# FPGA.net
KiCad netlist of a schematic drawn in Altium Designer
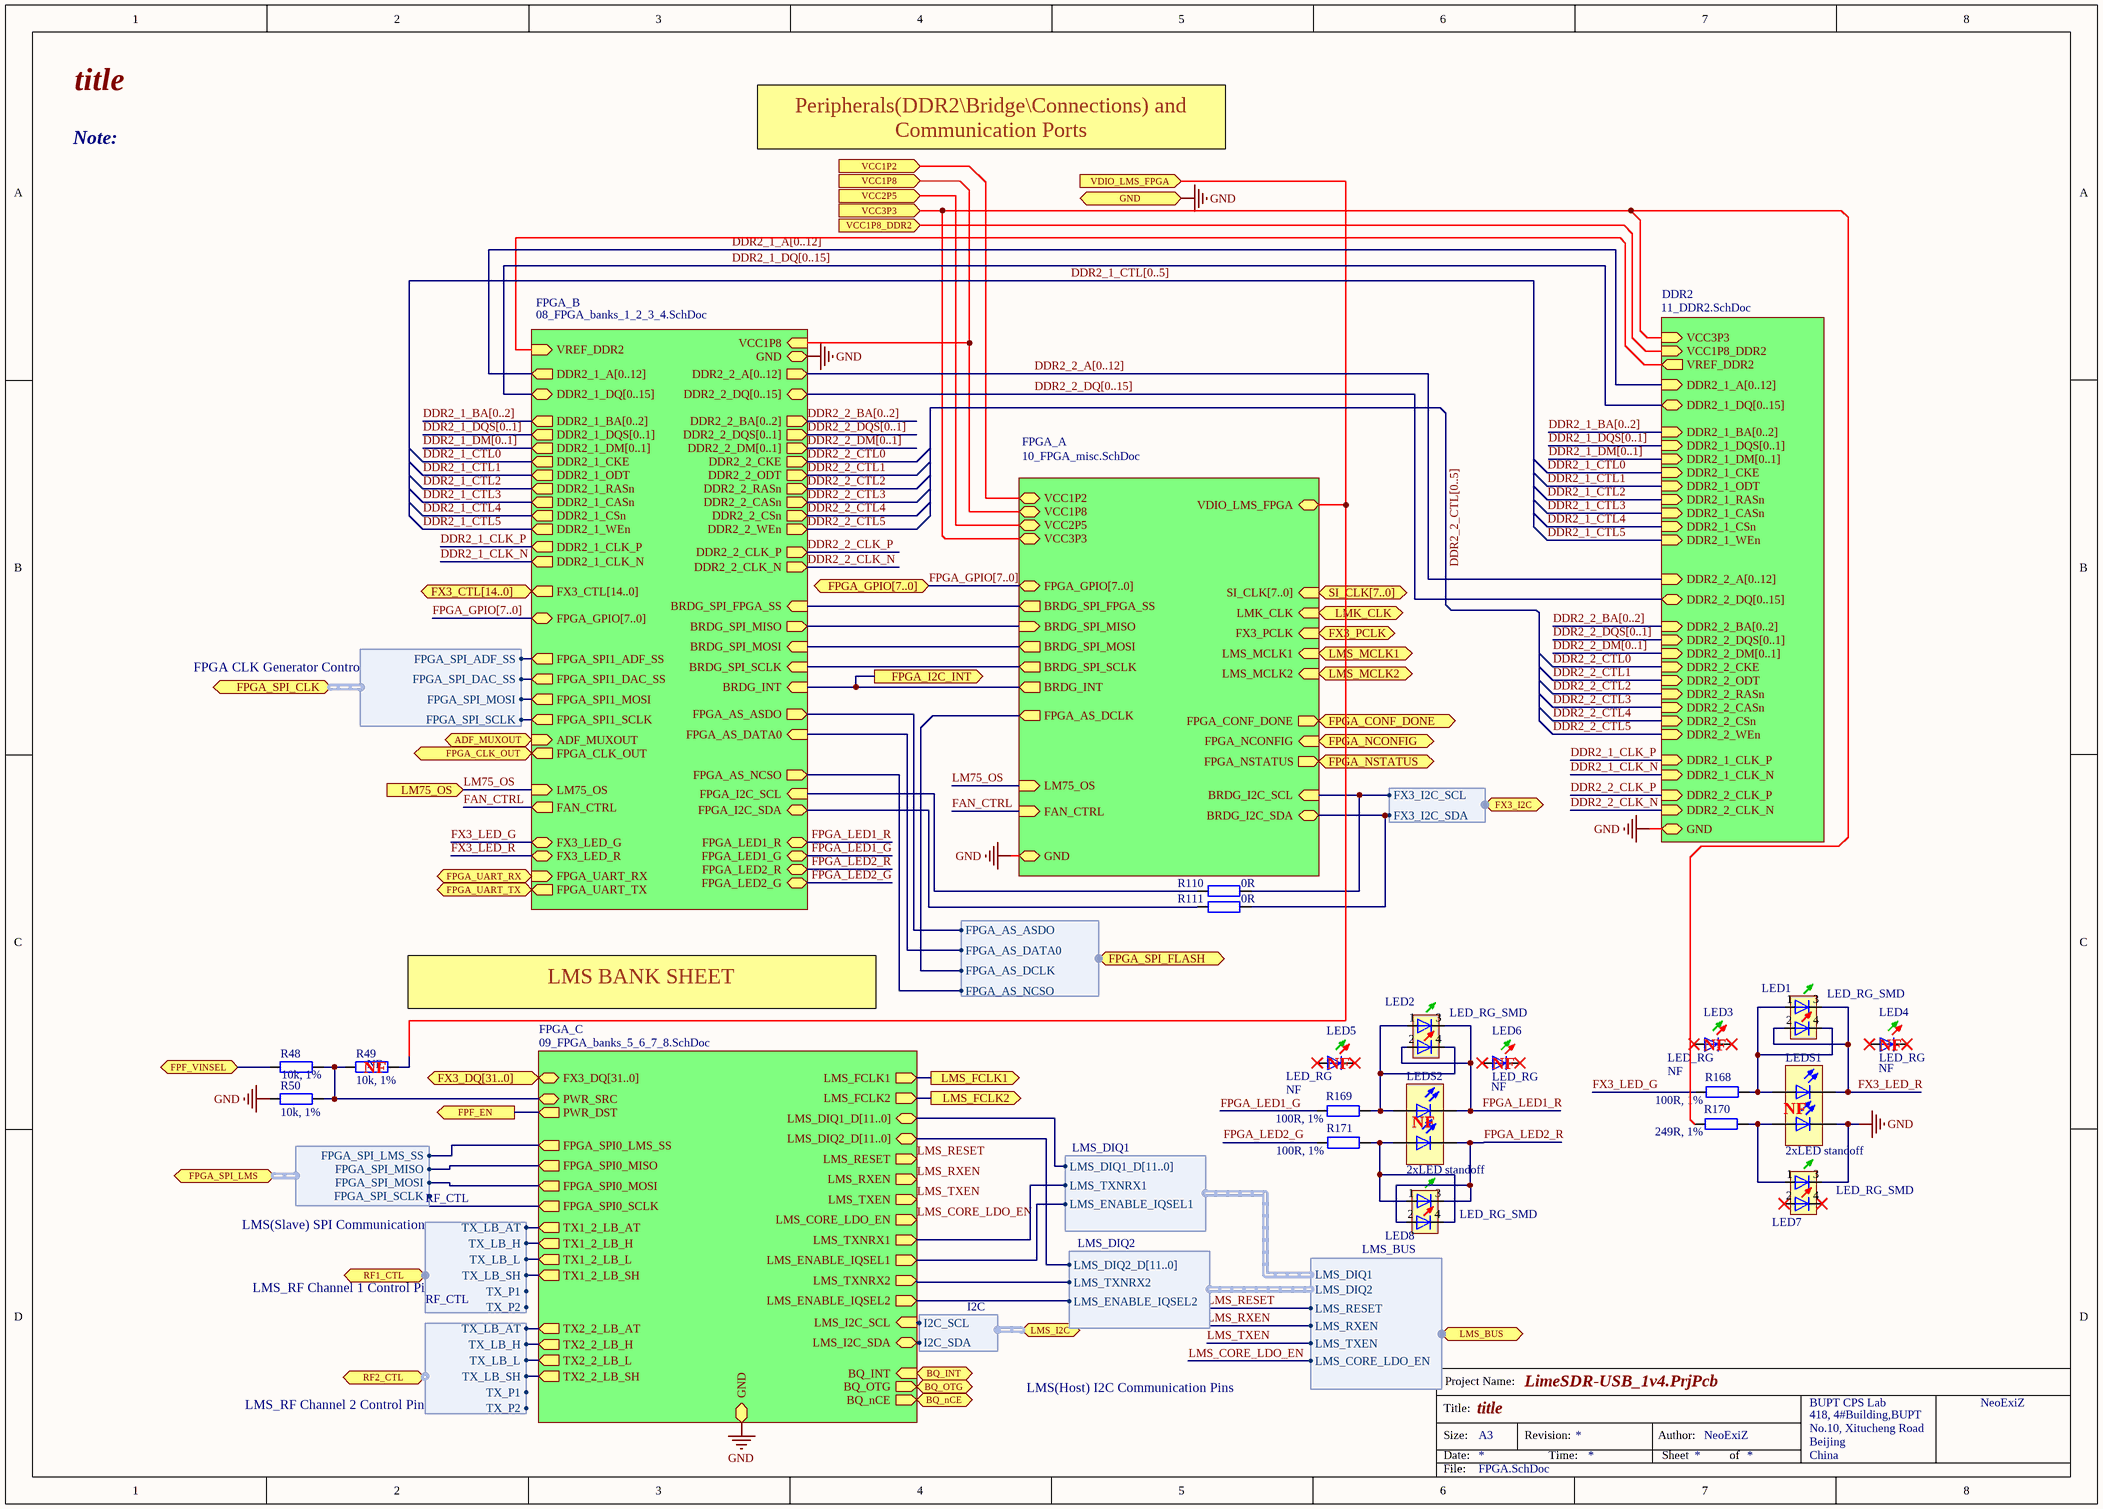
[diagram p0: FPGA.SchDoc]

(export (version "E")
  (design (tool "Eeschema 10.0.6"))
  (components
    (comp (ref "LED1")
      (value "LED_RG_SMD")
      (footprint "LED-2x0603")
      (fields (field (name "MANUFACTURER") "Avago Technologies US Inc."))
      (libsource (lib "LimeMicroAltiumLib_schLib") (part "LED_green_red_SMD"))
    )
    (comp (ref "LED2")
      (value "LED_RG_SMD")
      (footprint "LED-2x0603")
      (fields (field (name "MANUFACTURER") "Avago Technologies US Inc."))
      (libsource (lib "LimeMicroAltiumLib_schLib") (part "LED_green_red_SMD"))
    )
    (comp (ref "LED3")
      (value "LED_RG")
      (fields
        (field (name "MANUFACTURER") "Visual Communications Company - VCC")
        (field (name "ASSEMBLY INFO") "NF")
      )
      (libsource (lib "LimeMicroAltiumLib_schLib") (part "LED_green_red"))
    )
    (comp (ref "LED4")
      (value "LED_RG")
      (fields
        (field (name "MANUFACTURER") "Visual Communications Company - VCC")
        (field (name "ASSEMBLY INFO") "NF")
      )
      (libsource (lib "LimeMicroAltiumLib_schLib") (part "LED_green_red"))
    )
    (comp (ref "LED5")
      (value "LED_RG")
      (fields
        (field (name "MANUFACTURER") "Visual Communications Company - VCC")
        (field (name "ASSEMBLY INFO") "NF")
      )
      (libsource (lib "LimeMicroAltiumLib_schLib") (part "LED_green_red"))
    )
    (comp (ref "LED6")
      (value "LED_RG")
      (fields
        (field (name "MANUFACTURER") "Visual Communications Company - VCC")
        (field (name "ASSEMBLY INFO") "NF")
      )
      (libsource (lib "LimeMicroAltiumLib_schLib") (part "LED_green_red"))
    )
    (comp (ref "LED7")
      (value "LED_RG_SMD")
      (footprint "LED-2x0603")
      (fields (field (name "MANUFACTURER") "Avago Technologies US Inc."))
      (libsource (lib "LimeMicroAltiumLib_schLib") (part "LED_green_red_SMD"))
    )
    (comp (ref "LED8")
      (value "LED_RG_SMD")
      (footprint "LED-2x0603")
      (fields (field (name "MANUFACTURER") "Avago Technologies US Inc."))
      (libsource (lib "LimeMicroAltiumLib_schLib") (part "LED_green_red_SMD"))
    )
    (comp (ref "LEDS1")
      (value "2xLED standoff")
      (footprint "LED_STANDOFF_H-201C")
      (libsource (lib "LimeMicroAltiumLib_schLib") (part "LEDx2_STANDOFF"))
    )
    (comp (ref "LEDS2")
      (value "2xLED standoff")
      (footprint "LED_STANDOFF_H-201C")
      (libsource (lib "LimeMicroAltiumLib_schLib") (part "LEDx2_STANDOFF"))
    )
    (comp (ref "R48")
      (value "10k, 1%")
      (footprint "RES0402")
      (fields (field (name "MANUFACTURER") "Yageo") (field (name "TOLERANCE") "±1%"))
      (libsource (lib "LimeMicroAltiumLib_schLib") (part "Res_0402"))
    )
    (comp (ref "R49")
      (value "10k, 1%")
      (footprint "RES0402")
      (fields
        (field (name "ASSEMBLY INFO") "NF")
        (field (name "MANUFACTURER") "Yageo")
        (field (name "TOLERANCE") "±1%")
      )
      (libsource (lib "LimeMicroAltiumLib_schLib") (part "Res_0402"))
    )
    (comp (ref "R50")
      (value "10k, 1%")
      (footprint "RES0402")
      (fields (field (name "MANUFACTURER") "Yageo") (field (name "TOLERANCE") "±1%"))
      (libsource (lib "LimeMicroAltiumLib_schLib") (part "Res_0402"))
    )
    (comp (ref "R110")
      (value "0R")
      (footprint "RES0402")
      (fields (field (name "MANUFACTURER") "Yageo"))
      (libsource (lib "LimeFPGAboard_schLib") (part "Res_0402"))
    )
    (comp (ref "R111")
      (value "0R")
      (footprint "RES0402")
      (fields (field (name "MANUFACTURER") "Yageo"))
      (libsource (lib "LimeFPGAboard_schLib") (part "Res_0402"))
    )
    (comp (ref "R168")
      (value "100R, 1%")
      (footprint "RES0402")
      (fields (field (name "TOLERANCE") "±1%") (field (name "MANUFACTURER") "Stackpole Electronics Inc."))
      (libsource (lib "LimeMicroAltiumLib_schLib") (part "Res_0402"))
    )
    (comp (ref "R169")
      (value "100R, 1%")
      (footprint "RES0402")
      (fields (field (name "TOLERANCE") "±1%") (field (name "MANUFACTURER") "Stackpole Electronics Inc."))
      (libsource (lib "LimeMicroAltiumLib_schLib") (part "Res_0402"))
    )
    (comp (ref "R170")
      (value "249R, 1%")
      (footprint "RES0402")
      (fields (field (name "MANUFACTURER") "Stackpole Electronics Inc") (field (name "TOLERANCE") "±1%"))
      (libsource (lib "LimeMicroAltiumLib_schLib") (part "Res_0402"))
    )
    (comp (ref "R171")
      (value "100R, 1%")
      (footprint "RES0402")
      (fields (field (name "TOLERANCE") "±1%") (field (name "MANUFACTURER") "Stackpole Electronics Inc."))
      (libsource (lib "LimeMicroAltiumLib_schLib") (part "Res_0402"))
    )
  )
  (nets
    (net (code "149") (name "/BRDG_I2C_SCL") (class "Default")
      (node (ref "R110") (pin "2") (pinfunction "2_2") (pintype "passive"))
    )
    (net (code "150") (name "/BRDG_I2C_SDA") (class "Default")
      (node (ref "R111") (pin "2") (pinfunction "2_2") (pintype "passive"))
    )
    (net (code "185") (name "/FPF_VINSEL") (class "Default")
      (node (ref "R48") (pin "1") (pinfunction "1_1") (pintype "passive"))
    )
    (net (code "194") (name "/FPGA_I2C_SCL") (class "Default")
      (node (ref "R110") (pin "1") (pinfunction "1_1") (pintype "passive"))
    )
    (net (code "195") (name "/FPGA_I2C_SDA") (class "Default")
      (node (ref "R111") (pin "1") (pinfunction "1_1") (pintype "passive"))
    )
    (net (code "196") (name "/FPGA_LED1_G") (class "Default")
      (node (ref "R169") (pin "1") (pinfunction "1_1") (pintype "passive"))
    )
    (net (code "197") (name "/FPGA_LED1_R") (class "Default")
      (node (ref "LED2") (pin "2") (pinfunction "2_2") (pintype "power_in"))
      (node (ref "LED2") (pin "3") (pinfunction "3_3") (pintype "power_in"))
      (node (ref "LEDS2") (pin "K1") (pinfunction "C_K1") (pintype "power_in"))
    )
    (net (code "198") (name "/FPGA_LED2_G") (class "Default")
      (node (ref "R171") (pin "1") (pinfunction "1_1") (pintype "passive"))
    )
    (net (code "199") (name "/FPGA_LED2_R") (class "Default")
      (node (ref "LED8") (pin "2") (pinfunction "2_2") (pintype "power_in"))
      (node (ref "LED8") (pin "3") (pinfunction "3_3") (pintype "power_in"))
      (node (ref "LEDS2") (pin "K2") (pinfunction "C_K2") (pintype "power_in"))
    )
    (net (code "214") (name "/FX3_LED_G") (class "Default")
      (node (ref "R168") (pin "1") (pinfunction "1_1") (pintype "passive"))
    )
    (net (code "215") (name "/FX3_LED_R") (class "Default")
      (node (ref "LED1") (pin "2") (pinfunction "2_2") (pintype "power_in"))
      (node (ref "LED1") (pin "3") (pinfunction "3_3") (pintype "power_in"))
      (node (ref "LEDS1") (pin "K1") (pinfunction "C_K1") (pintype "power_in"))
    )
    (net (code "236") (name "/PWR_SRC") (class "Default")
      (node (ref "R48") (pin "2") (pinfunction "2_2") (pintype "passive"))
      (node (ref "R49") (pin "1") (pinfunction "1_1") (pintype "passive"))
      (node (ref "R50") (pin "2") (pinfunction "2_2") (pintype "passive"))
    )
    (net (code "250") (name "/VCC3P3") (class "Default")
      (node (ref "R170") (pin "1") (pinfunction "1_1") (pintype "passive"))
    )
    (net (code "251") (name "/VDIO_LMS_FPGA") (class "Default")
      (node (ref "R49") (pin "2") (pinfunction "2_2") (pintype "passive"))
    )
    (net (code "261") (name "GND") (class "Default")
      (node (ref "LED7") (pin "3") (pinfunction "3_3") (pintype "power_in"))
      (node (ref "LEDS1") (pin "K2") (pinfunction "C_K2") (pintype "power_in"))
      (node (ref "R50") (pin "1") (pinfunction "1_1") (pintype "passive"))
    )
    (net (code "262") (name "Net-(LED1-Pad1)") (class "Default")
      (node (ref "LED1") (pin "1") (pinfunction "1_1") (pintype "power_in"))
      (node (ref "LED1") (pin "4") (pinfunction "4_4") (pintype "power_in"))
      (node (ref "LEDS1") (pin "A1") (pinfunction "A_A1") (pintype "power_in"))
      (node (ref "R168") (pin "2") (pinfunction "2_2") (pintype "passive"))
    )
    (net (code "263") (name "Net-(LED2-Pad1)") (class "Default")
      (node (ref "LED2") (pin "1") (pinfunction "1_1") (pintype "power_in"))
      (node (ref "LED2") (pin "4") (pinfunction "4_4") (pintype "power_in"))
      (node (ref "LEDS2") (pin "A1") (pinfunction "A_A1") (pintype "power_in"))
      (node (ref "R169") (pin "2") (pinfunction "2_2") (pintype "passive"))
    )
    (net (code "264") (name "Net-(LED7-Pad1)") (class "Default")
      (node (ref "LED7") (pin "1") (pinfunction "1_1") (pintype "power_in"))
      (node (ref "LEDS1") (pin "A2") (pinfunction "A_A2") (pintype "power_in"))
      (node (ref "R170") (pin "2") (pinfunction "2_2") (pintype "passive"))
    )
    (net (code "265") (name "Net-(LED8-Pad1)") (class "Default")
      (node (ref "LED8") (pin "1") (pinfunction "1_1") (pintype "power_in"))
      (node (ref "LED8") (pin "4") (pinfunction "4_4") (pintype "power_in"))
      (node (ref "LEDS2") (pin "A2") (pinfunction "A_A2") (pintype "power_in"))
      (node (ref "R171") (pin "2") (pinfunction "2_2") (pintype "passive"))
    )
    (net (code "266") (name "unconnected-(LED3-C-PadK)") (class "Default")
      (node (ref "LED3") (pin "K") (pinfunction "C_K") (pintype "power_in+no_connect"))
    )
    (net (code "267") (name "unconnected-(LED3-PadA)") (class "Default")
      (node (ref "LED3") (pin "A") (pinfunction "A_A") (pintype "power_in+no_connect"))
    )
    (net (code "268") (name "unconnected-(LED4-C-PadK)") (class "Default")
      (node (ref "LED4") (pin "K") (pinfunction "C_K") (pintype "power_in+no_connect"))
    )
    (net (code "269") (name "unconnected-(LED4-PadA)") (class "Default")
      (node (ref "LED4") (pin "A") (pinfunction "A_A") (pintype "power_in+no_connect"))
    )
    (net (code "270") (name "unconnected-(LED5-C-PadK)") (class "Default")
      (node (ref "LED5") (pin "K") (pinfunction "C_K") (pintype "power_in+no_connect"))
    )
    (net (code "271") (name "unconnected-(LED5-PadA)") (class "Default")
      (node (ref "LED5") (pin "A") (pinfunction "A_A") (pintype "power_in+no_connect"))
    )
    (net (code "272") (name "unconnected-(LED6-C-PadK)") (class "Default")
      (node (ref "LED6") (pin "K") (pinfunction "C_K") (pintype "power_in+no_connect"))
    )
    (net (code "273") (name "unconnected-(LED6-PadA)") (class "Default")
      (node (ref "LED6") (pin "A") (pinfunction "A_A") (pintype "power_in+no_connect"))
    )
    (net (code "274") (name "unconnected-(LED7-Pad2)") (class "Default")
      (node (ref "LED7") (pin "2") (pinfunction "2_2") (pintype "power_in+no_connect"))
    )
    (net (code "275") (name "unconnected-(LED7-Pad4)") (class "Default")
      (node (ref "LED7") (pin "4") (pinfunction "4_4") (pintype "power_in+no_connect"))
    )
  )
)
